# Max756Breakout.net
KiCad netlist of a schematic drawn in EAGLE
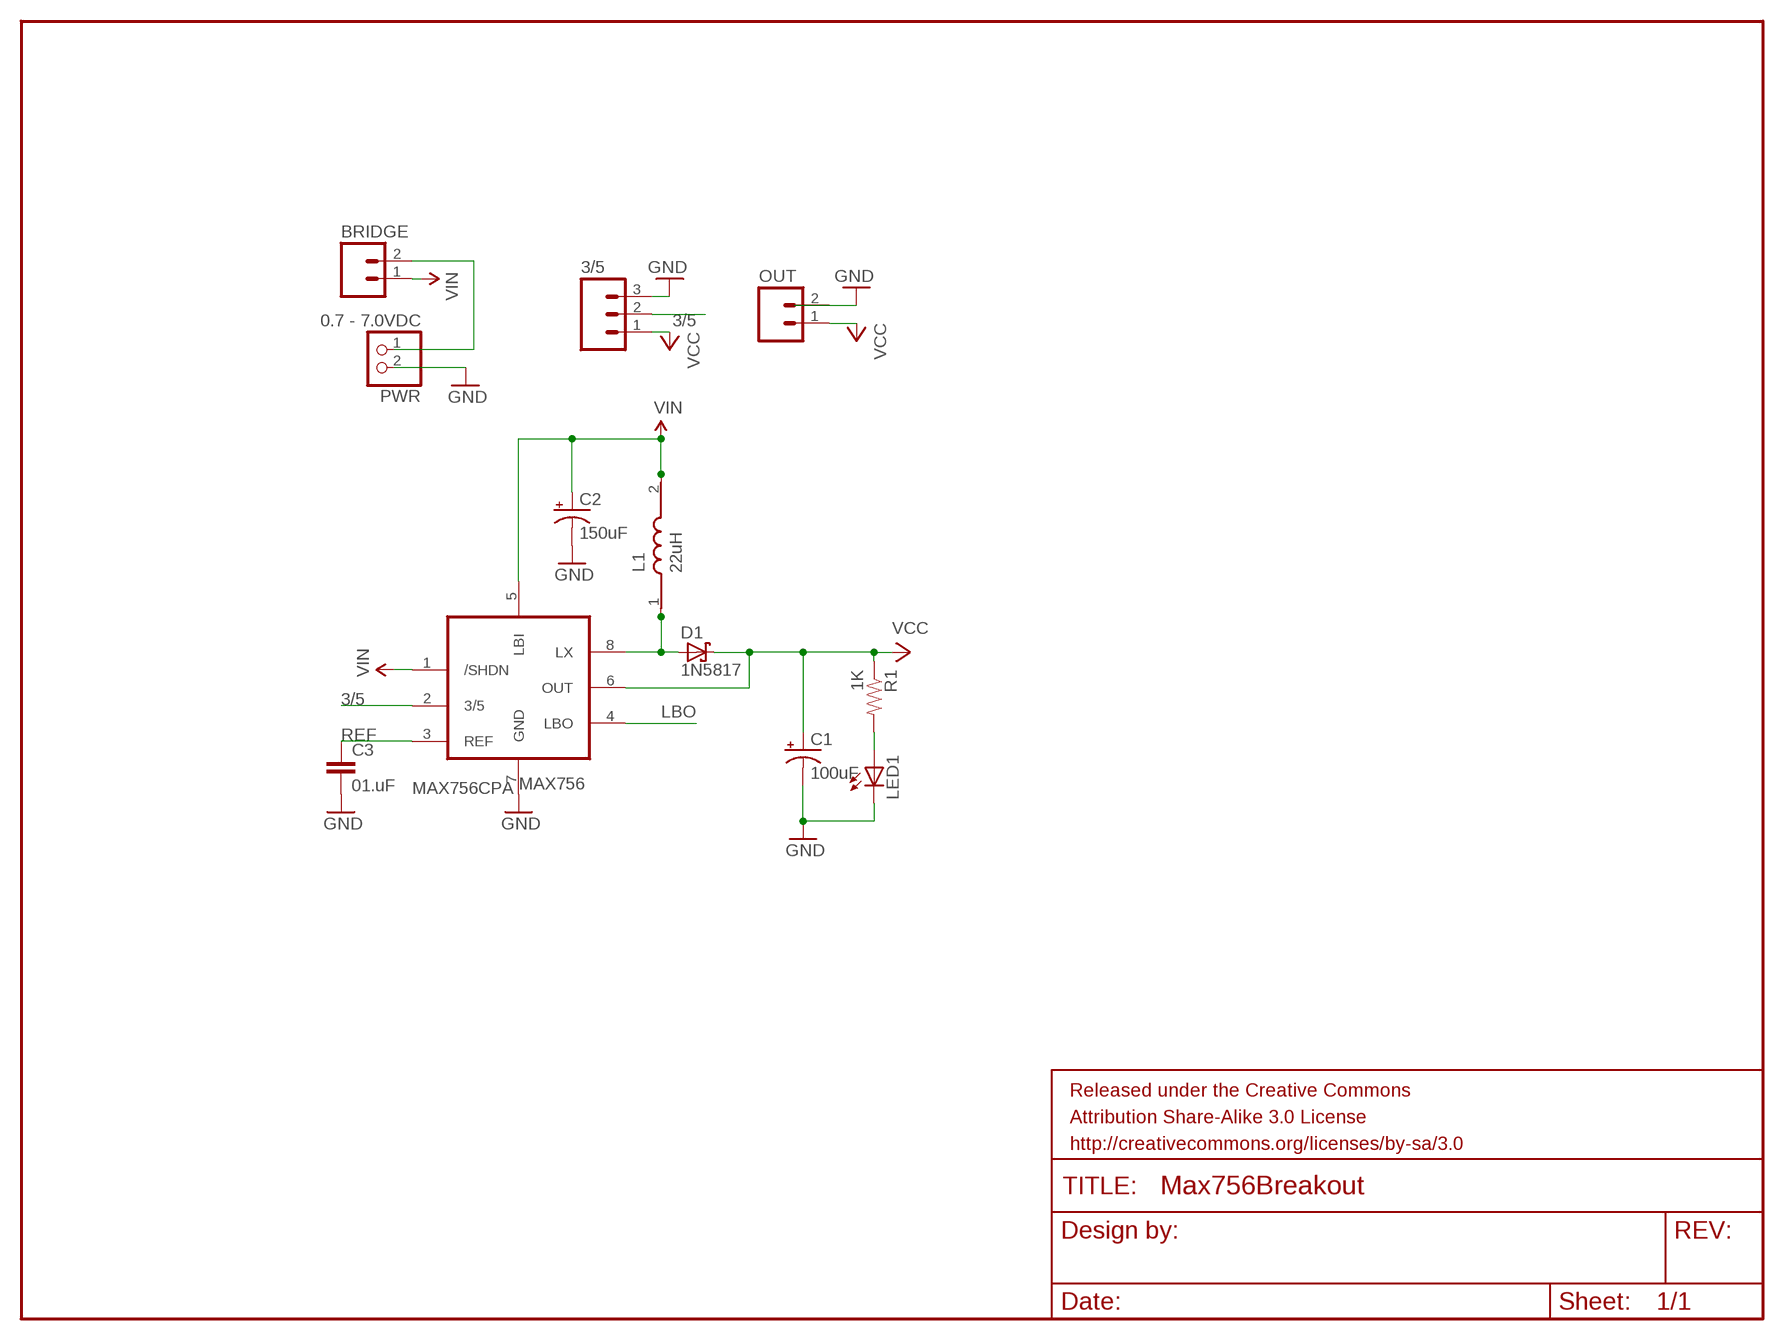
[diagram p0: schematic, sheet 1]

(export (version "E")
  (design (tool "Eeschema 10.0.6"))
  (components
    (comp (ref "3/5")
      (value "M03LOCK")
      (footprint "eagle-import:1X03_LOCK")
      (libsource (lib "eagle-import") (part "M03LOCK"))
    )
    (comp (ref "BRIDGE")
      (value "M02LOCK")
      (footprint "eagle-import:1X02_LOCK")
      (libsource (lib "eagle-import") (part "M02LOCK"))
    )
    (comp (ref "C1")
      (value "100uF")
      (footprint "eagle-import:CPOL-RADIAL-10UF-25V")
      (libsource (lib "eagle-import") (part "CAP_POLPTH2"))
    )
    (comp (ref "C2")
      (value "150uF")
      (footprint "eagle-import:CPOL-RADIAL-10UF-25V")
      (libsource (lib "eagle-import") (part "CAP_POLPTH2"))
    )
    (comp (ref "C3")
      (value "01.uF")
      (footprint "eagle-import:CAP-PTH-SMALL2")
      (libsource (lib "eagle-import") (part "CAPPTH2"))
    )
    (comp (ref "D1")
      (value "1N5817")
      (footprint "eagle-import:F126Z12")
      (libsource (lib "eagle-import") (part "SCHOTTKY-DIODEF126Z12"))
    )
    (comp (ref "FRAME1")
      (value "FRAME-LETTER")
      (footprint "eagle-import:CREATIVE_COMMONS")
      (libsource (lib "eagle-import") (part "FRAME-LETTER"))
    )
    (comp (ref "L1")
      (value "22uH")
      (footprint "eagle-import:82114R")
      (libsource (lib "eagle-import") (part "82114R"))
    )
    (comp (ref "LED1")
      (value "LED3MM")
      (footprint "eagle-import:LED3MM")
      (libsource (lib "eagle-import") (part "LED3MM"))
    )
    (comp (ref "MAX756")
      (value "MAX756CPA")
      (footprint "eagle-import:DIL08")
      (libsource (lib "eagle-import") (part "MAX756CPA"))
    )
    (comp (ref "OUT")
      (value "M02LOCK")
      (footprint "eagle-import:1X02_LOCK")
      (libsource (lib "eagle-import") (part "M02LOCK"))
    )
    (comp (ref "PWR")
      (value "0.7 - 7.0VDC")
      (footprint "eagle-import:JST-PH-2-THM-RA")
      (libsource (lib "eagle-import") (part "JST_2PIN-THM-RA"))
    )
    (comp (ref "R1")
      (value "1K")
      (footprint "eagle-import:AXIAL-0.2")
      (libsource (lib "eagle-import") (part "RESISTORAXIAL-0.2"))
    )
  )
  (nets
    (net (code "1") (name "/3{slash}5") (class "Default")
      (node (ref "3/5") (pin "2") (pinfunction "2_2") (pintype "passive"))
      (node (ref "MAX756") (pin "2") (pinfunction "3/5_2") (pintype "bidirectional"))
    )
    (net (code "2") (name "/LBO") (class "Default")
      (node (ref "MAX756") (pin "4") (pinfunction "LBO_4") (pintype "input"))
    )
    (net (code "3") (name "/REF") (class "Default")
      (node (ref "C3") (pin "1") (pinfunction "1_1") (pintype "passive"))
      (node (ref "MAX756") (pin "3") (pinfunction "REF_3") (pintype "passive"))
    )
    (net (code "4") (name "GND") (class "Default")
      (node (ref "3/5") (pin "3") (pinfunction "3_3") (pintype "passive"))
      (node (ref "C1") (pin "2") (pinfunction "-_2") (pintype "passive"))
      (node (ref "C2") (pin "2") (pinfunction "-_2") (pintype "passive"))
      (node (ref "C3") (pin "2") (pinfunction "2_2") (pintype "passive"))
      (node (ref "LED1") (pin "K") (pinfunction "C_K") (pintype "passive"))
      (node (ref "MAX756") (pin "7") (pinfunction "GND_7") (pintype "power_in"))
      (node (ref "OUT") (pin "2") (pinfunction "2_2") (pintype "passive"))
      (node (ref "PWR") (pin "2") (pinfunction "1_2") (pintype "passive"))
    )
    (net (code "5") (name "Net-(MAX756-LX)") (class "Default")
      (node (ref "D1") (pin "A") (pinfunction "A_A") (pintype "passive"))
      (node (ref "L1") (pin "1") (pinfunction "1_1") (pintype "passive"))
      (node (ref "MAX756") (pin "8") (pinfunction "LX_8") (pintype "output"))
    )
    (net (code "6") (name "Net-(PWR-2)") (class "Default")
      (node (ref "BRIDGE") (pin "2") (pinfunction "2_2") (pintype "passive"))
      (node (ref "PWR") (pin "1") (pinfunction "2_1") (pintype "passive"))
    )
    (net (code "7") (name "Net-(R1-2)") (class "Default")
      (node (ref "LED1") (pin "A") (pinfunction "A_A") (pintype "passive"))
      (node (ref "R1") (pin "P$2") (pinfunction "2_P$2") (pintype "passive"))
    )
    (net (code "8") (name "VCC") (class "Default")
      (node (ref "3/5") (pin "1") (pinfunction "1_1") (pintype "passive"))
      (node (ref "C1") (pin "1") (pinfunction "+_1") (pintype "passive"))
      (node (ref "D1") (pin "C") (pinfunction "C_C") (pintype "passive"))
      (node (ref "MAX756") (pin "6") (pinfunction "OUT_6") (pintype "output"))
      (node (ref "OUT") (pin "1") (pinfunction "1_1") (pintype "passive"))
      (node (ref "R1") (pin "P$1") (pinfunction "1_P$1") (pintype "passive"))
    )
    (net (code "9") (name "VIN") (class "Default")
      (node (ref "BRIDGE") (pin "1") (pinfunction "1_1") (pintype "passive"))
      (node (ref "C2") (pin "1") (pinfunction "+_1") (pintype "passive"))
      (node (ref "L1") (pin "2") (pinfunction "2_2") (pintype "passive"))
      (node (ref "MAX756") (pin "1") (pinfunction "/SHDN_1") (pintype "input"))
      (node (ref "MAX756") (pin "5") (pinfunction "LBI_5") (pintype "input"))
    )
  )
)
